# KegWasher_1_6_Schematic.net
KiCad netlist of a schematic drawn in EasyEDA
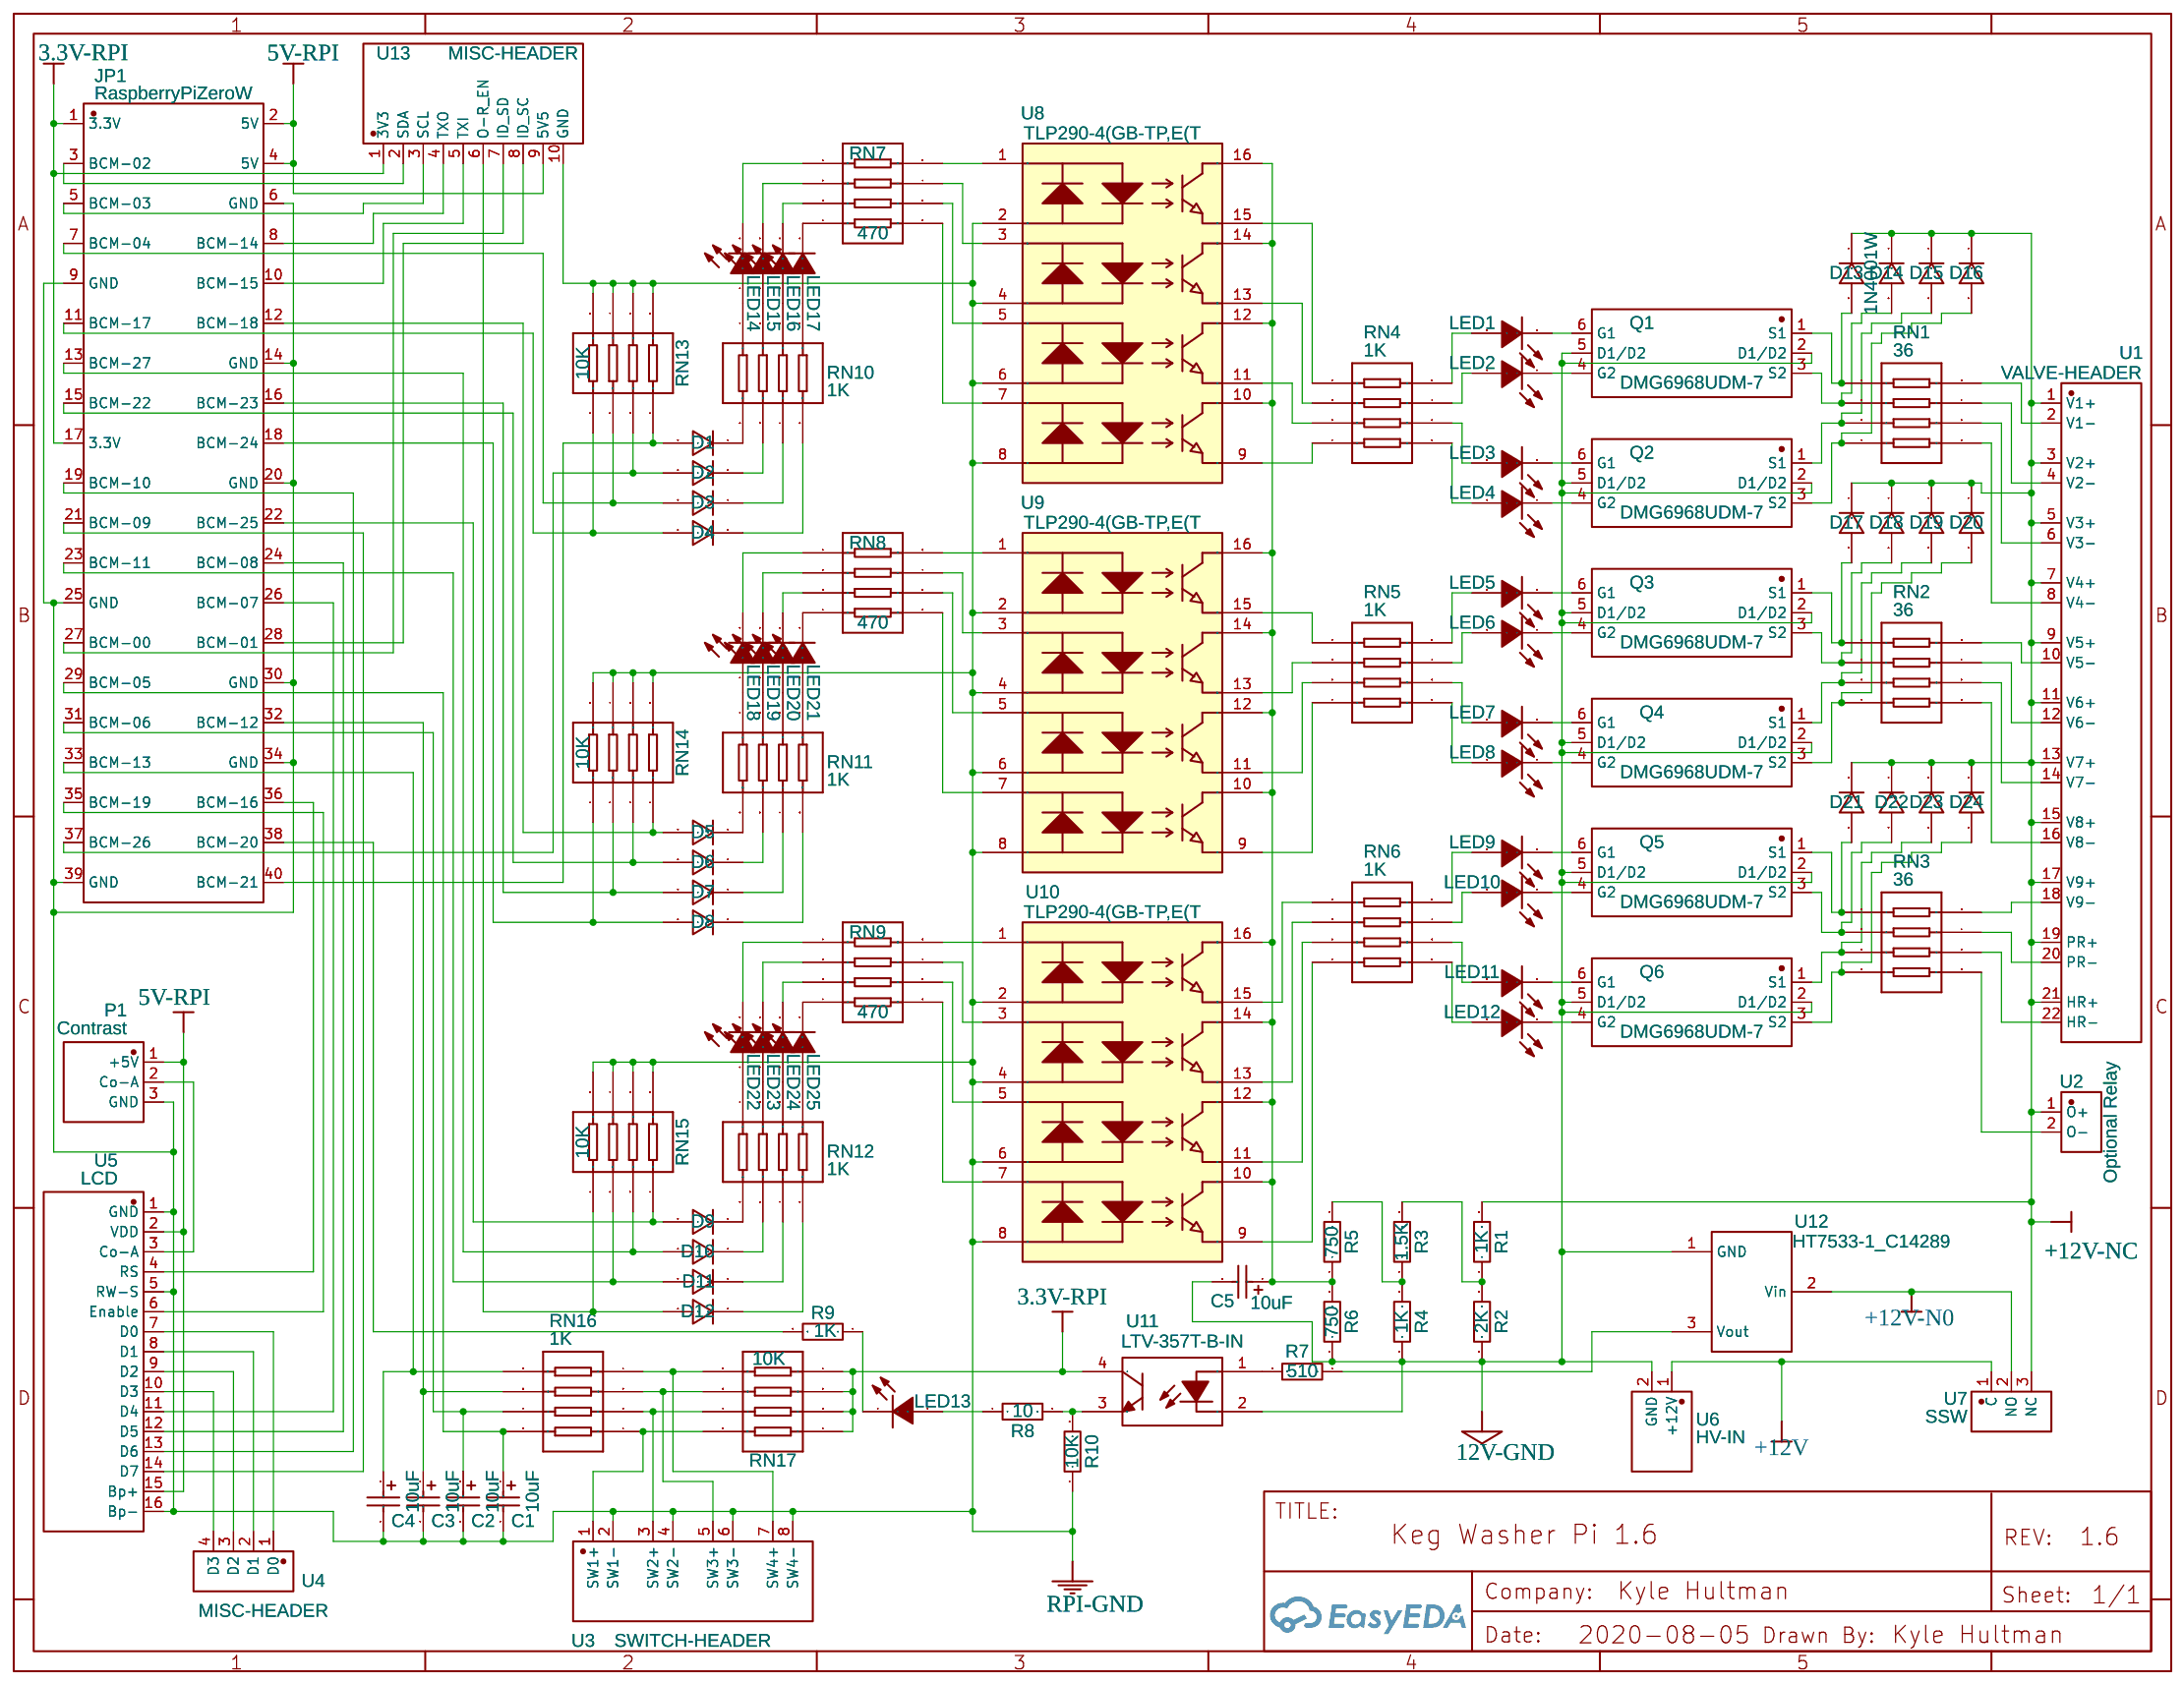
[diagram p0: schematic sheet]

(export (version "E")
  (design (tool "Eeschema 10.0.6"))
  (components
    (comp (ref "C1")
      (value "10uF")
      (fields
        (field (name "BOM_Manufacturer Part") "TAJA106K016RNJ")
        (field (name "BOM_Supplier Part") "C7171")
      )
      (libsource (lib "") (part "TAJA106K016RNJ"))
    )
    (comp (ref "C2")
      (value "10uF")
      (fields
        (field (name "BOM_Manufacturer Part") "TAJA106K016RNJ")
        (field (name "BOM_Supplier Part") "C7171")
      )
      (libsource (lib "") (part "TAJA106K016RNJ"))
    )
    (comp (ref "C3")
      (value "10uF")
      (fields
        (field (name "BOM_Manufacturer Part") "TAJA106K016RNJ")
        (field (name "BOM_Supplier Part") "C7171")
      )
      (libsource (lib "") (part "TAJA106K016RNJ"))
    )
    (comp (ref "C4")
      (value "10uF")
      (fields
        (field (name "BOM_Manufacturer Part") "TAJA106K016RNJ")
        (field (name "BOM_Supplier Part") "C7171")
      )
      (libsource (lib "") (part "TAJA106K016RNJ"))
    )
    (comp (ref "C5")
      (value "10uF")
      (fields
        (field (name "BOM_Manufacturer Part") "TAJA106K016RNJ")
        (field (name "BOM_Supplier Part") "C7171")
      )
      (libsource (lib "") (part "TAJA106K016RNJ_1"))
    )
    (comp (ref "D1")
      (value "1N4148W_C81598")
      (fields (field (name "BOM_Manufacturer Part") "1N4148W") (field (name "BOM_Supplier Part") "C81598"))
      (libsource (lib "") (part "1N4148W_C81598"))
    )
    (comp (ref "D2")
      (value "1N4148W_C81598")
      (fields (field (name "BOM_Manufacturer Part") "1N4148W") (field (name "BOM_Supplier Part") "C81598"))
      (libsource (lib "") (part "1N4148W_C81598"))
    )
    (comp (ref "D3")
      (value "1N4148W_C81598")
      (fields (field (name "BOM_Manufacturer Part") "1N4148W") (field (name "BOM_Supplier Part") "C81598"))
      (libsource (lib "") (part "1N4148W_C81598"))
    )
    (comp (ref "D4")
      (value "1N4148W_C81598")
      (fields (field (name "BOM_Manufacturer Part") "1N4148W") (field (name "BOM_Supplier Part") "C81598"))
      (libsource (lib "") (part "1N4148W_C81598"))
    )
    (comp (ref "D5")
      (value "1N4148W_C81598")
      (fields (field (name "BOM_Manufacturer Part") "1N4148W") (field (name "BOM_Supplier Part") "C81598"))
      (libsource (lib "") (part "1N4148W_C81598"))
    )
    (comp (ref "D6")
      (value "1N4148W_C81598")
      (fields (field (name "BOM_Manufacturer Part") "1N4148W") (field (name "BOM_Supplier Part") "C81598"))
      (libsource (lib "") (part "1N4148W_C81598"))
    )
    (comp (ref "D7")
      (value "1N4148W_C81598")
      (fields (field (name "BOM_Manufacturer Part") "1N4148W") (field (name "BOM_Supplier Part") "C81598"))
      (libsource (lib "") (part "1N4148W_C81598"))
    )
    (comp (ref "D8")
      (value "1N4148W_C81598")
      (fields (field (name "BOM_Manufacturer Part") "1N4148W") (field (name "BOM_Supplier Part") "C81598"))
      (libsource (lib "") (part "1N4148W_C81598"))
    )
    (comp (ref "D9")
      (value "1N4148W_C81598")
      (fields (field (name "BOM_Manufacturer Part") "1N4148W") (field (name "BOM_Supplier Part") "C81598"))
      (libsource (lib "") (part "1N4148W_C81598"))
    )
    (comp (ref "D10")
      (value "1N4148W_C81598")
      (fields (field (name "BOM_Manufacturer Part") "1N4148W") (field (name "BOM_Supplier Part") "C81598"))
      (libsource (lib "") (part "1N4148W_C81598"))
    )
    (comp (ref "D11")
      (value "1N4148W_C81598")
      (fields (field (name "BOM_Manufacturer Part") "1N4148W") (field (name "BOM_Supplier Part") "C81598"))
      (libsource (lib "") (part "1N4148W_C81598"))
    )
    (comp (ref "D12")
      (value "1N4148W_C81598")
      (fields (field (name "BOM_Manufacturer Part") "1N4148W") (field (name "BOM_Supplier Part") "C81598"))
      (libsource (lib "") (part "1N4148W_C81598"))
    )
    (comp (ref "D13")
      (value "1N4001W")
      (fields (field (name "BOM_Supplier Part") "C162732"))
      (libsource (lib "") (part "1N4001W"))
    )
    (comp (ref "D14")
      (value "1N4001W")
      (fields (field (name "BOM_Supplier Part") "C162732"))
      (libsource (lib "") (part "1N4001W"))
    )
    (comp (ref "D15")
      (value "1N4001W")
      (fields (field (name "BOM_Supplier Part") "C162732"))
      (libsource (lib "") (part "1N4001W"))
    )
    (comp (ref "D16")
      (value "1N4001W")
      (fields (field (name "BOM_Supplier Part") "C162732"))
      (libsource (lib "") (part "1N4001W"))
    )
    (comp (ref "D17")
      (value "1N4001W")
      (fields (field (name "BOM_Supplier Part") "C162732"))
      (libsource (lib "") (part "1N4001W"))
    )
    (comp (ref "D18")
      (value "1N4001W")
      (fields (field (name "BOM_Supplier Part") "C162732"))
      (libsource (lib "") (part "1N4001W"))
    )
    (comp (ref "D19")
      (value "1N4001W")
      (fields (field (name "BOM_Supplier Part") "C162732"))
      (libsource (lib "") (part "1N4001W"))
    )
    (comp (ref "D20")
      (value "1N4001W")
      (fields (field (name "BOM_Supplier Part") "C162732"))
      (libsource (lib "") (part "1N4001W"))
    )
    (comp (ref "D21")
      (value "1N4001W")
      (fields (field (name "BOM_Supplier Part") "C162732"))
      (libsource (lib "") (part "1N4001W"))
    )
    (comp (ref "D22")
      (value "1N4001W")
      (fields (field (name "BOM_Supplier Part") "C162732"))
      (libsource (lib "") (part "1N4001W"))
    )
    (comp (ref "D23")
      (value "1N4001W")
      (fields (field (name "BOM_Supplier Part") "C162732"))
      (libsource (lib "") (part "1N4001W"))
    )
    (comp (ref "D24")
      (value "1N4001W")
      (fields (field (name "BOM_Supplier Part") "C162732"))
      (libsource (lib "") (part "1N4001W"))
    )
    (comp (ref "JP1") (value "RaspberryPiZeroW") (libsource (lib "") (part "RaspberryPiZeroW")))
    (comp (ref "LED1")
      (value "17-21SUYC/TR8")
      (fields (field (name "BOM_Supplier Part") "C2296"))
      (libsource (lib "") (part "17-21SUYC/TR8"))
    )
    (comp (ref "LED2")
      (value "17-21SUYC/TR8")
      (fields (field (name "BOM_Supplier Part") "C2296"))
      (libsource (lib "") (part "17-21SUYC/TR8"))
    )
    (comp (ref "LED3")
      (value "17-21SUYC/TR8")
      (fields (field (name "BOM_Supplier Part") "C2296"))
      (libsource (lib "") (part "17-21SUYC/TR8"))
    )
    (comp (ref "LED4")
      (value "17-21SUYC/TR8")
      (fields (field (name "BOM_Supplier Part") "C2296"))
      (libsource (lib "") (part "17-21SUYC/TR8"))
    )
    (comp (ref "LED5")
      (value "17-21SUYC/TR8")
      (fields (field (name "BOM_Supplier Part") "C2296"))
      (libsource (lib "") (part "17-21SUYC/TR8"))
    )
    (comp (ref "LED6")
      (value "17-21SUYC/TR8")
      (fields (field (name "BOM_Supplier Part") "C2296"))
      (libsource (lib "") (part "17-21SUYC/TR8"))
    )
    (comp (ref "LED7")
      (value "17-21SUYC/TR8")
      (fields (field (name "BOM_Supplier Part") "C2296"))
      (libsource (lib "") (part "17-21SUYC/TR8"))
    )
    (comp (ref "LED8")
      (value "17-21SUYC/TR8")
      (fields (field (name "BOM_Supplier Part") "C2296"))
      (libsource (lib "") (part "17-21SUYC/TR8"))
    )
    (comp (ref "LED9")
      (value "17-21SUYC/TR8")
      (fields (field (name "BOM_Supplier Part") "C2296"))
      (libsource (lib "") (part "17-21SUYC/TR8"))
    )
    (comp (ref "LED10")
      (value "17-21SUYC/TR8")
      (fields (field (name "BOM_Supplier Part") "C2296"))
      (libsource (lib "") (part "17-21SUYC/TR8"))
    )
    (comp (ref "LED11")
      (value "17-21SUYC/TR8")
      (fields (field (name "BOM_Supplier Part") "C2296"))
      (libsource (lib "") (part "17-21SUYC/TR8"))
    )
    (comp (ref "LED12")
      (value "17-21SUYC/TR8")
      (fields (field (name "BOM_Supplier Part") "C2296"))
      (libsource (lib "") (part "17-21SUYC/TR8"))
    )
    (comp (ref "LED13")
      (value "17-21SUYC/TR8")
      (fields (field (name "BOM_Supplier Part") "C2296"))
      (libsource (lib "") (part "17-21SUYC/TR8_1"))
    )
    (comp (ref "LED14")
      (value "19-217/R6C-AL1M2VY/3T")
      (fields (field (name "BOM_Supplier Part") "C72044"))
      (libsource (lib "") (part "19-217/R6C-AL1M2VY/3T"))
    )
    (comp (ref "LED15")
      (value "19-217/R6C-AL1M2VY/3T")
      (fields (field (name "BOM_Supplier Part") "C72044"))
      (libsource (lib "") (part "19-217/R6C-AL1M2VY/3T"))
    )
    (comp (ref "LED16")
      (value "19-217/R6C-AL1M2VY/3T")
      (fields (field (name "BOM_Supplier Part") "C72044"))
      (libsource (lib "") (part "19-217/R6C-AL1M2VY/3T"))
    )
    (comp (ref "LED17")
      (value "19-217/R6C-AL1M2VY/3T")
      (fields (field (name "BOM_Supplier Part") "C72044"))
      (libsource (lib "") (part "19-217/R6C-AL1M2VY/3T"))
    )
    (comp (ref "LED18")
      (value "19-217/R6C-AL1M2VY/3T")
      (fields (field (name "BOM_Supplier Part") "C72044"))
      (libsource (lib "") (part "19-217/R6C-AL1M2VY/3T"))
    )
    (comp (ref "LED19")
      (value "19-217/R6C-AL1M2VY/3T")
      (fields (field (name "BOM_Supplier Part") "C72044"))
      (libsource (lib "") (part "19-217/R6C-AL1M2VY/3T"))
    )
    (comp (ref "LED20")
      (value "19-217/R6C-AL1M2VY/3T")
      (fields (field (name "BOM_Supplier Part") "C72044"))
      (libsource (lib "") (part "19-217/R6C-AL1M2VY/3T"))
    )
    (comp (ref "LED21")
      (value "19-217/R6C-AL1M2VY/3T")
      (fields (field (name "BOM_Supplier Part") "C72044"))
      (libsource (lib "") (part "19-217/R6C-AL1M2VY/3T"))
    )
    (comp (ref "LED22")
      (value "19-217/R6C-AL1M2VY/3T")
      (fields (field (name "BOM_Supplier Part") "C72044"))
      (libsource (lib "") (part "19-217/R6C-AL1M2VY/3T"))
    )
    (comp (ref "LED23")
      (value "19-217/R6C-AL1M2VY/3T")
      (fields (field (name "BOM_Supplier Part") "C72044"))
      (libsource (lib "") (part "19-217/R6C-AL1M2VY/3T"))
    )
    (comp (ref "LED24")
      (value "19-217/R6C-AL1M2VY/3T")
      (fields (field (name "BOM_Supplier Part") "C72044"))
      (libsource (lib "") (part "19-217/R6C-AL1M2VY/3T"))
    )
    (comp (ref "LED25")
      (value "19-217/R6C-AL1M2VY/3T")
      (fields (field (name "BOM_Supplier Part") "C72044"))
      (libsource (lib "") (part "19-217/R6C-AL1M2VY/3T"))
    )
    (comp (ref "P1") (value "Contrast") (libsource (lib "") (part "Contrast")))
    (comp (ref "Q1")
      (value "DMG6968UDM-7")
      (fields (field (name "BOM_Supplier Part") "C151635"))
      (libsource (lib "") (part "DMG6968UDM-7"))
    )
    (comp (ref "Q2")
      (value "DMG6968UDM-7")
      (fields (field (name "BOM_Supplier Part") "C151635"))
      (libsource (lib "") (part "DMG6968UDM-7"))
    )
    (comp (ref "Q3")
      (value "DMG6968UDM-7")
      (fields (field (name "BOM_Supplier Part") "C151635"))
      (libsource (lib "") (part "DMG6968UDM-7"))
    )
    (comp (ref "Q4")
      (value "DMG6968UDM-7")
      (fields (field (name "BOM_Supplier Part") "C151635"))
      (libsource (lib "") (part "DMG6968UDM-7"))
    )
    (comp (ref "Q5")
      (value "DMG6968UDM-7")
      (fields (field (name "BOM_Supplier Part") "C151635"))
      (libsource (lib "") (part "DMG6968UDM-7"))
    )
    (comp (ref "Q6")
      (value "DMG6968UDM-7")
      (fields (field (name "BOM_Supplier Part") "C151635"))
      (libsource (lib "") (part "DMG6968UDM-7"))
    )
    (comp (ref "R1")
      (value "1K")
      (fields
        (field (name "BOM_Manufacturer Part") "0805W8F1001T5E")
        (field (name "BOM_Supplier Part") "C17513")
      )
      (libsource (lib "") (part "0805W8F1001T5E_1"))
    )
    (comp (ref "R2")
      (value "2K")
      (fields
        (field (name "BOM_Manufacturer Part") "0805W8F2001T5E")
        (field (name "BOM_Supplier Part") "C17604")
      )
      (libsource (lib "") (part "0805W8F2001T5E"))
    )
    (comp (ref "R3")
      (value "1.5K")
      (fields
        (field (name "BOM_Manufacturer Part") "0805W8F1501T5E")
        (field (name "BOM_Supplier Part") "C4310")
      )
      (libsource (lib "") (part "0805W8F1501T5E"))
    )
    (comp (ref "R4")
      (value "1K")
      (fields
        (field (name "BOM_Manufacturer Part") "0805W8F1001T5E")
        (field (name "BOM_Supplier Part") "C17513")
      )
      (libsource (lib "") (part "0805W8F1001T5E_1"))
    )
    (comp (ref "R5")
      (value "750")
      (fields
        (field (name "BOM_Manufacturer Part") "0603WAF7500T5E")
        (field (name "BOM_Supplier Part") "C23241")
      )
      (libsource (lib "") (part "0603WAF7500T5E"))
    )
    (comp (ref "R6")
      (value "750")
      (fields
        (field (name "BOM_Manufacturer Part") "0603WAF7500T5E")
        (field (name "BOM_Supplier Part") "C23241")
      )
      (libsource (lib "") (part "0603WAF7500T5E"))
    )
    (comp (ref "R7")
      (value "510")
      (fields
        (field (name "BOM_Manufacturer Part") "0603WAF5100T5E")
        (field (name "BOM_Supplier Part") "C23193")
      )
      (libsource (lib "") (part "0603WAF5100T5E"))
    )
    (comp (ref "R8")
      (value "10")
      (fields
        (field (name "BOM_Manufacturer Part") "0603WAF100JT5E")
        (field (name "BOM_Supplier Part") "C22859")
      )
      (libsource (lib "") (part "0603WAF100JT5E"))
    )
    (comp (ref "R9")
      (value "1K")
      (fields
        (field (name "BOM_Manufacturer Part") "0805W8F1001T5E")
        (field (name "BOM_Supplier Part") "C17513")
      )
      (libsource (lib "") (part "0805W8F1001T5E"))
    )
    (comp (ref "R10")
      (value "10K")
      (fields
        (field (name "BOM_Manufacturer Part") "1206W4F1002T5E")
        (field (name "BOM_Supplier Part") "C17902")
      )
      (libsource (lib "") (part "1206W4F1002T5E"))
    )
    (comp (ref "RN1")
      (value "36")
      (fields
        (field (name "BOM_Manufacturer Part") "4D02WGJ0360TCE")
        (field (name "BOM_Supplier Part") "C25502")
      )
      (libsource (lib "") (part "4D02WGJ0360TCE"))
    )
    (comp (ref "RN2")
      (value "36")
      (fields
        (field (name "BOM_Manufacturer Part") "4D02WGJ0360TCE")
        (field (name "BOM_Supplier Part") "C25502")
      )
      (libsource (lib "") (part "4D02WGJ0360TCE"))
    )
    (comp (ref "RN3")
      (value "36")
      (fields
        (field (name "BOM_Manufacturer Part") "4D02WGJ0360TCE")
        (field (name "BOM_Supplier Part") "C25502")
      )
      (libsource (lib "") (part "4D02WGJ0360TCE"))
    )
    (comp (ref "RN4")
      (value "1K")
      (fields
        (field (name "BOM_Manufacturer Part") "4D02WGJ0102TCE")
        (field (name "BOM_Supplier Part") "C25726")
      )
      (libsource (lib "") (part "4D02WGJ0102TCE"))
    )
    (comp (ref "RN5")
      (value "1K")
      (fields
        (field (name "BOM_Manufacturer Part") "4D02WGJ0102TCE")
        (field (name "BOM_Supplier Part") "C25726")
      )
      (libsource (lib "") (part "4D02WGJ0102TCE"))
    )
    (comp (ref "RN6")
      (value "1K")
      (fields
        (field (name "BOM_Manufacturer Part") "4D02WGJ0102TCE")
        (field (name "BOM_Supplier Part") "C25726")
      )
      (libsource (lib "") (part "4D02WGJ0102TCE"))
    )
    (comp (ref "RN7")
      (value "470")
      (fields
        (field (name "BOM_Manufacturer Part") "4D03WGJ0471T5E")
        (field (name "BOM_Supplier Part") "C25510")
      )
      (libsource (lib "") (part "4D03WGJ0471T5E"))
    )
    (comp (ref "RN8")
      (value "470")
      (fields
        (field (name "BOM_Manufacturer Part") "4D03WGJ0471T5E")
        (field (name "BOM_Supplier Part") "C25510")
      )
      (libsource (lib "") (part "4D03WGJ0471T5E"))
    )
    (comp (ref "RN9")
      (value "470")
      (fields
        (field (name "BOM_Manufacturer Part") "4D03WGJ0471T5E")
        (field (name "BOM_Supplier Part") "C25510")
      )
      (libsource (lib "") (part "4D03WGJ0471T5E"))
    )
    (comp (ref "RN10")
      (value "1K")
      (fields
        (field (name "BOM_Manufacturer Part") "4D02WGJ0102TCE")
        (field (name "BOM_Supplier Part") "C25726")
      )
      (libsource (lib "") (part "4D02WGJ0102TCE_2"))
    )
    (comp (ref "RN11")
      (value "1K")
      (fields
        (field (name "BOM_Manufacturer Part") "4D02WGJ0102TCE")
        (field (name "BOM_Supplier Part") "C25726")
      )
      (libsource (lib "") (part "4D02WGJ0102TCE_2"))
    )
    (comp (ref "RN12")
      (value "1K")
      (fields
        (field (name "BOM_Manufacturer Part") "4D02WGJ0102TCE")
        (field (name "BOM_Supplier Part") "C25726")
      )
      (libsource (lib "") (part "4D02WGJ0102TCE_2"))
    )
    (comp (ref "RN13")
      (value "10K")
      (fields
        (field (name "BOM_Manufacturer Part") "4D02WGJ0103TCE")
        (field (name "BOM_Supplier Part") "C25725")
      )
      (libsource (lib "") (part "4D02WGJ0103TCE"))
    )
    (comp (ref "RN14")
      (value "10K")
      (fields
        (field (name "BOM_Manufacturer Part") "4D02WGJ0103TCE")
        (field (name "BOM_Supplier Part") "C25725")
      )
      (libsource (lib "") (part "4D02WGJ0103TCE"))
    )
    (comp (ref "RN15")
      (value "10K")
      (fields
        (field (name "BOM_Manufacturer Part") "4D02WGJ0103TCE")
        (field (name "BOM_Supplier Part") "C25725")
      )
      (libsource (lib "") (part "4D02WGJ0103TCE"))
    )
    (comp (ref "RN16")
      (value "1K")
      (fields
        (field (name "BOM_Manufacturer Part") "4D02WGJ0102TCE")
        (field (name "BOM_Supplier Part") "C25726")
      )
      (libsource (lib "") (part "4D02WGJ0102TCE_1"))
    )
    (comp (ref "RN17")
      (value "10K")
      (fields
        (field (name "BOM_Manufacturer Part") "4D02WGJ0103TCE")
        (field (name "BOM_Supplier Part") "C25725")
      )
      (libsource (lib "") (part "4D02WGJ0103TCE_1"))
    )
    (comp (ref "U1") (value "VALVE-HEADER") (libsource (lib "") (part "VALVE-HEADER")))
    (comp (ref "U2") (value "Optional Relay") (libsource (lib "") (part "Optional Relay")))
    (comp (ref "U3") (value "SWITCH-HEADER") (libsource (lib "") (part "SWITCH-HEADER")))
    (comp (ref "U4") (value "MISC-HEADER") (libsource (lib "") (part "MISC-HEADER")))
    (comp (ref "U5") (value "LCD") (libsource (lib "") (part "LCD")))
    (comp (ref "U6") (value "HV-IN") (libsource (lib "") (part "HV-IN")))
    (comp (ref "U7") (value "SSW") (libsource (lib "") (part "SSW")))
    (comp (ref "U8")
      (value "TLP290-4(GB-TP,E(T")
      (fields (field (name "BOM_Supplier Part") "C39031"))
      (libsource (lib "") (part "TLP290-4(GB-TP,E(T"))
    )
    (comp (ref "U9")
      (value "TLP290-4(GB-TP,E(T")
      (fields (field (name "BOM_Supplier Part") "C39031"))
      (libsource (lib "") (part "TLP290-4(GB-TP,E(T"))
    )
    (comp (ref "U10")
      (value "TLP290-4(GB-TP,E(T")
      (fields (field (name "BOM_Supplier Part") "C39031"))
      (libsource (lib "") (part "TLP290-4(GB-TP,E(T"))
    )
    (comp (ref "U11")
      (value "LTV-357T-B-IN")
      (fields (field (name "BOM_Supplier Part") "C406713"))
      (libsource (lib "") (part "LTV-357T-B-IN"))
    )
    (comp (ref "U12")
      (value "HT7533-1_C14289")
      (fields (field (name "BOM_Manufacturer Part") "HT7533-1") (field (name "BOM_Supplier Part") "C14289"))
      (libsource (lib "") (part "HT7533-1_C14289"))
    )
    (comp (ref "U13") (value "MISC-HEADER") (libsource (lib "") (part "MISC-HEADER_1")))
  )
  (nets
    (net (code "1") (name "+12V") (class "Default")
      (node (ref "U6") (pin "1") (pinfunction "+12V_1") (pintype "unspecified"))
      (node (ref "U7") (pin "1") (pinfunction "C_1") (pintype "unspecified"))
    )
    (net (code "2") (name "+12V-N0") (class "Default")
      (node (ref "U12") (pin "2") (pinfunction "Vin_2") (pintype "unspecified"))
      (node (ref "U7") (pin "2") (pinfunction "NO_2") (pintype "unspecified"))
    )
    (net (code "3") (name "+12V-NC") (class "Default")
      (node (ref "D13") (pin "1") (pinfunction "C_1") (pintype "unspecified"))
      (node (ref "D14") (pin "1") (pinfunction "C_1") (pintype "unspecified"))
      (node (ref "D15") (pin "1") (pinfunction "C_1") (pintype "unspecified"))
      (node (ref "D16") (pin "1") (pinfunction "C_1") (pintype "unspecified"))
      (node (ref "D17") (pin "1") (pinfunction "C_1") (pintype "unspecified"))
      (node (ref "D18") (pin "1") (pinfunction "C_1") (pintype "unspecified"))
      (node (ref "D19") (pin "1") (pinfunction "C_1") (pintype "unspecified"))
      (node (ref "D20") (pin "1") (pinfunction "C_1") (pintype "unspecified"))
      (node (ref "D21") (pin "1") (pinfunction "C_1") (pintype "unspecified"))
      (node (ref "D22") (pin "1") (pinfunction "C_1") (pintype "unspecified"))
      (node (ref "D23") (pin "1") (pinfunction "C_1") (pintype "unspecified"))
      (node (ref "D24") (pin "1") (pinfunction "C_1") (pintype "unspecified"))
      (node (ref "R1") (pin "2") (pinfunction "2_2") (pintype "input"))
      (node (ref "U1") (pin "1") (pinfunction "V1+_1") (pintype "unspecified"))
      (node (ref "U1") (pin "11") (pinfunction "V6+_11") (pintype "unspecified"))
      (node (ref "U1") (pin "13") (pinfunction "V7+_13") (pintype "unspecified"))
      (node (ref "U1") (pin "15") (pinfunction "V8+_15") (pintype "unspecified"))
      (node (ref "U1") (pin "17") (pinfunction "V9+_17") (pintype "unspecified"))
      (node (ref "U1") (pin "19") (pinfunction "PR+_19") (pintype "unspecified"))
      (node (ref "U1") (pin "21") (pinfunction "HR+_21") (pintype "unspecified"))
      (node (ref "U1") (pin "3") (pinfunction "V2+_3") (pintype "unspecified"))
      (node (ref "U1") (pin "5") (pinfunction "V3+_5") (pintype "unspecified"))
      (node (ref "U1") (pin "7") (pinfunction "V4+_7") (pintype "unspecified"))
      (node (ref "U1") (pin "9") (pinfunction "V5+_9") (pintype "unspecified"))
      (node (ref "U2") (pin "1") (pinfunction "O+_1") (pintype "unspecified"))
      (node (ref "U7") (pin "3") (pinfunction "NC_3") (pintype "unspecified"))
    )
    (net (code "4") (name "3.3V-RPI") (class "Default")
      (node (ref "JP1") (pin "1") (pinfunction "3.3V_1") (pintype "unspecified"))
      (node (ref "JP1") (pin "17") (pinfunction "3.3V_17") (pintype "unspecified"))
      (node (ref "RN17") (pin "1") (pinfunction "1_1") (pintype "input"))
      (node (ref "RN17") (pin "2") (pinfunction "2_2") (pintype "input"))
      (node (ref "RN17") (pin "3") (pinfunction "3_3") (pintype "input"))
      (node (ref "RN17") (pin "4") (pinfunction "4_4") (pintype "input"))
      (node (ref "U11") (pin "4") (pinfunction "4_4") (pintype "unspecified"))
      (node (ref "U13") (pin "1") (pinfunction "3V3_1") (pintype "unspecified"))
    )
    (net (code "5") (name "5V-RPI") (class "Default")
      (node (ref "JP1") (pin "2") (pinfunction "5V_2") (pintype "unspecified"))
      (node (ref "JP1") (pin "4") (pinfunction "5V_4") (pintype "unspecified"))
      (node (ref "P1") (pin "1") (pinfunction "+5V_1") (pintype "unspecified"))
      (node (ref "U13") (pin "9") (pinfunction "5V5_9") (pintype "unspecified"))
      (node (ref "U5") (pin "15") (pinfunction "Bp+_15") (pintype "unspecified"))
      (node (ref "U5") (pin "2") (pinfunction "VDD_2") (pintype "unspecified"))
    )
    (net (code "6") (name "12V-GND") (class "Default")
      (node (ref "C5") (pin "2") (pinfunction "2_2") (pintype "input"))
      (node (ref "Q1") (pin "2") (pinfunction "D1/D2_2") (pintype "unspecified"))
      (node (ref "Q1") (pin "5") (pinfunction "D1/D2_5") (pintype "unspecified"))
      (node (ref "Q2") (pin "2") (pinfunction "D1/D2_2") (pintype "unspecified"))
      (node (ref "Q2") (pin "5") (pinfunction "D1/D2_5") (pintype "unspecified"))
      (node (ref "Q3") (pin "2") (pinfunction "D1/D2_2") (pintype "unspecified"))
      (node (ref "Q3") (pin "5") (pinfunction "D1/D2_5") (pintype "unspecified"))
      (node (ref "Q4") (pin "2") (pinfunction "D1/D2_2") (pintype "unspecified"))
      (node (ref "Q4") (pin "5") (pinfunction "D1/D2_5") (pintype "unspecified"))
      (node (ref "Q5") (pin "2") (pinfunction "D1/D2_2") (pintype "unspecified"))
      (node (ref "Q5") (pin "5") (pinfunction "D1/D2_5") (pintype "unspecified"))
      (node (ref "Q6") (pin "2") (pinfunction "D1/D2_2") (pintype "unspecified"))
      (node (ref "Q6") (pin "5") (pinfunction "D1/D2_5") (pintype "unspecified"))
      (node (ref "R2") (pin "1") (pinfunction "1_1") (pintype "input"))
      (node (ref "R4") (pin "1") (pinfunction "1_1") (pintype "input"))
      (node (ref "R6") (pin "1") (pinfunction "1_1") (pintype "input"))
      (node (ref "U11") (pin "2") (pinfunction "2_2") (pintype "unspecified"))
      (node (ref "U12") (pin "1") (pinfunction "GND_1") (pintype "unspecified"))
      (node (ref "U6") (pin "2") (pinfunction "GND_2") (pintype "unspecified"))
    )
    (net (code "7") (name "Net-(C5-Pad1)") (class "Default")
      (node (ref "C5") (pin "1") (pinfunction "1_1") (pintype "input"))
      (node (ref "R5") (pin "1") (pinfunction "1_1") (pintype "input"))
      (node (ref "R6") (pin "2") (pinfunction "2_2") (pintype "input"))
      (node (ref "U10") (pin "10") (pinfunction "10_10") (pintype "input"))
      (node (ref "U10") (pin "12") (pinfunction "12_12") (pintype "input"))
      (node (ref "U10") (pin "14") (pinfunction "14_14") (pintype "input"))
      (node (ref "U10") (pin "16") (pinfunction "16_16") (pintype "input"))
      (node (ref "U8") (pin "10") (pinfunction "10_10") (pintype "input"))
      (node (ref "U8") (pin "12") (pinfunction "12_12") (pintype "input"))
      (node (ref "U8") (pin "14") (pinfunction "14_14") (pintype "input"))
      (node (ref "U8") (pin "16") (pinfunction "16_16") (pintype "input"))
      (node (ref "U9") (pin "10") (pinfunction "10_10") (pintype "input"))
      (node (ref "U9") (pin "12") (pinfunction "12_12") (pintype "input"))
      (node (ref "U9") (pin "14") (pinfunction "14_14") (pintype "input"))
      (node (ref "U9") (pin "16") (pinfunction "16_16") (pintype "input"))
    )
    (net (code "8") (name "Net-(D1-A)") (class "Default")
      (node (ref "D1") (pin "2") (pinfunction "A_2") (pintype "unspecified"))
      (node (ref "JP1") (pin "40") (pinfunction "BCM-21_40") (pintype "unspecified"))
      (node (ref "RN13") (pin "4") (pinfunction "4_4") (pintype "input"))
    )
    (net (code "9") (name "Net-(D1-K)") (class "Default")
      (node (ref "D1") (pin "1") (pinfunction "K_1") (pintype "unspecified"))
      (node (ref "RN10") (pin "5") (pinfunction "5_5") (pintype "input"))
    )
    (net (code "10") (name "Net-(D2-A)") (class "Default")
      (node (ref "D2") (pin "2") (pinfunction "A_2") (pintype "unspecified"))
      (node (ref "JP1") (pin "37") (pinfunction "BCM-26_37") (pintype "unspecified"))
      (node (ref "RN13") (pin "3") (pinfunction "3_3") (pintype "input"))
    )
    (net (code "11") (name "Net-(D2-K)") (class "Default")
      (node (ref "D2") (pin "1") (pinfunction "K_1") (pintype "unspecified"))
      (node (ref "RN10") (pin "6") (pinfunction "6_6") (pintype "input"))
    )
    (net (code "12") (name "Net-(D3-A)") (class "Default")
      (node (ref "D3") (pin "2") (pinfunction "A_2") (pintype "unspecified"))
      (node (ref "JP1") (pin "7") (pinfunction "BCM-04_7") (pintype "unspecified"))
      (node (ref "RN13") (pin "2") (pinfunction "2_2") (pintype "input"))
    )
    (net (code "13") (name "Net-(D3-K)") (class "Default")
      (node (ref "D3") (pin "1") (pinfunction "K_1") (pintype "unspecified"))
      (node (ref "RN10") (pin "7") (pinfunction "7_7") (pintype "input"))
    )
    (net (code "14") (name "Net-(D4-A)") (class "Default")
      (node (ref "D4") (pin "2") (pinfunction "A_2") (pintype "unspecified"))
      (node (ref "JP1") (pin "11") (pinfunction "BCM-17_11") (pintype "unspecified"))
      (node (ref "RN13") (pin "1") (pinfunction "1_1") (pintype "input"))
    )
    (net (code "15") (name "Net-(D4-K)") (class "Default")
      (node (ref "D4") (pin "1") (pinfunction "K_1") (pintype "unspecified"))
      (node (ref "RN10") (pin "8") (pinfunction "8_8") (pintype "input"))
    )
    (net (code "16") (name "Net-(D5-A)") (class "Default")
      (node (ref "D5") (pin "2") (pinfunction "A_2") (pintype "unspecified"))
      (node (ref "JP1") (pin "12") (pinfunction "BCM-18_12") (pintype "unspecified"))
      (node (ref "RN14") (pin "4") (pinfunction "4_4") (pintype "input"))
    )
    (net (code "17") (name "Net-(D5-K)") (class "Default")
      (node (ref "D5") (pin "1") (pinfunction "K_1") (pintype "unspecified"))
      (node (ref "RN11") (pin "5") (pinfunction "5_5") (pintype "input"))
    )
    (net (code "18") (name "Net-(D6-A)") (class "Default")
      (node (ref "D6") (pin "2") (pinfunction "A_2") (pintype "unspecified"))
      (node (ref "JP1") (pin "15") (pinfunction "BCM-22_15") (pintype "unspecified"))
      (node (ref "RN14") (pin "3") (pinfunction "3_3") (pintype "input"))
    )
    (net (code "19") (name "Net-(D6-K)") (class "Default")
      (node (ref "D6") (pin "1") (pinfunction "K_1") (pintype "unspecified"))
      (node (ref "RN11") (pin "6") (pinfunction "6_6") (pintype "input"))
    )
    (net (code "20") (name "Net-(D7-A)") (class "Default")
      (node (ref "D7") (pin "2") (pinfunction "A_2") (pintype "unspecified"))
      (node (ref "JP1") (pin "16") (pinfunction "BCM-23_16") (pintype "unspecified"))
      (node (ref "RN14") (pin "2") (pinfunction "2_2") (pintype "input"))
    )
    (net (code "21") (name "Net-(D7-K)") (class "Default")
      (node (ref "D7") (pin "1") (pinfunction "K_1") (pintype "unspecified"))
      (node (ref "RN11") (pin "7") (pinfunction "7_7") (pintype "input"))
    )
    (net (code "22") (name "Net-(D8-A)") (class "Default")
      (node (ref "D8") (pin "2") (pinfunction "A_2") (pintype "unspecified"))
      (node (ref "JP1") (pin "18") (pinfunction "BCM-24_18") (pintype "unspecified"))
      (node (ref "RN14") (pin "1") (pinfunction "1_1") (pintype "input"))
    )
    (net (code "23") (name "Net-(D8-K)") (class "Default")
      (node (ref "D8") (pin "1") (pinfunction "K_1") (pintype "unspecified"))
      (node (ref "RN11") (pin "8") (pinfunction "8_8") (pintype "input"))
    )
    (net (code "24") (name "Net-(D9-A)") (class "Default")
      (node (ref "D9") (pin "2") (pinfunction "A_2") (pintype "unspecified"))
      (node (ref "JP1") (pin "22") (pinfunction "BCM-25_22") (pintype "unspecified"))
      (node (ref "RN15") (pin "4") (pinfunction "4_4") (pintype "input"))
    )
    (net (code "25") (name "Net-(D9-K)") (class "Default")
      (node (ref "D9") (pin "1") (pinfunction "K_1") (pintype "unspecified"))
      (node (ref "RN12") (pin "5") (pinfunction "5_5") (pintype "input"))
    )
    (net (code "26") (name "Net-(D10-A)") (class "Default")
      (node (ref "D10") (pin "2") (pinfunction "A_2") (pintype "unspecified"))
      (node (ref "JP1") (pin "13") (pinfunction "BCM-27_13") (pintype "unspecified"))
      (node (ref "RN15") (pin "3") (pinfunction "3_3") (pintype "input"))
    )
    (net (code "27") (name "Net-(D10-K)") (class "Default")
      (node (ref "D10") (pin "1") (pinfunction "K_1") (pintype "unspecified"))
      (node (ref "RN12") (pin "6") (pinfunction "6_6") (pintype "input"))
    )
    (net (code "28") (name "Net-(D11-A)") (class "Default")
      (node (ref "D11") (pin "2") (pinfunction "A_2") (pintype "unspecified"))
      (node (ref "JP1") (pin "23") (pinfunction "BCM-11_23") (pintype "unspecified"))
      (node (ref "RN15") (pin "2") (pinfunction "2_2") (pintype "input"))
    )
    (net (code "29") (name "Net-(D11-K)") (class "Default")
      (node (ref "D11") (pin "1") (pinfunction "K_1") (pintype "unspecified"))
      (node (ref "RN12") (pin "7") (pinfunction "7_7") (pintype "input"))
    )
    (net (code "30") (name "Net-(D12-A)") (class "Default")
      (node (ref "D12") (pin "2") (pinfunction "A_2") (pintype "unspecified"))
      (node (ref "RN15") (pin "1") (pinfunction "1_1") (pintype "input"))
      (node (ref "U13") (pin "6") (pinfunction "O-R_EN_6") (pintype "unspecified"))
    )
    (net (code "31") (name "Net-(D12-K)") (class "Default")
      (node (ref "D12") (pin "1") (pinfunction "K_1") (pintype "unspecified"))
      (node (ref "RN12") (pin "8") (pinfunction "8_8") (pintype "input"))
    )
    (net (code "32") (name "Net-(D13-A)") (class "Default")
      (node (ref "D13") (pin "2") (pinfunction "A_2") (pintype "unspecified"))
      (node (ref "Q1") (pin "1") (pinfunction "S1_1") (pintype "unspecified"))
      (node (ref "RN1") (pin "1") (pinfunction "1_1") (pintype "input"))
    )
    (net (code "33") (name "Net-(D14-A)") (class "Default")
      (node (ref "D14") (pin "2") (pinfunction "A_2") (pintype "unspecified"))
      (node (ref "Q1") (pin "3") (pinfunction "S2_3") (pintype "unspecified"))
      (node (ref "RN1") (pin "2") (pinfunction "2_2") (pintype "input"))
    )
    (net (code "34") (name "Net-(D15-A)") (class "Default")
      (node (ref "D15") (pin "2") (pinfunction "A_2") (pintype "unspecified"))
      (node (ref "Q2") (pin "1") (pinfunction "S1_1") (pintype "unspecified"))
      (node (ref "RN1") (pin "3") (pinfunction "3_3") (pintype "input"))
    )
    (net (code "35") (name "Net-(D16-A)") (class "Default")
      (node (ref "D16") (pin "2") (pinfunction "A_2") (pintype "unspecified"))
      (node (ref "Q2") (pin "3") (pinfunction "S2_3") (pintype "unspecified"))
      (node (ref "RN1") (pin "4") (pinfunction "4_4") (pintype "input"))
    )
    (net (code "36") (name "Net-(D17-A)") (class "Default")
      (node (ref "D17") (pin "2") (pinfunction "A_2") (pintype "unspecified"))
      (node (ref "Q3") (pin "1") (pinfunction "S1_1") (pintype "unspecified"))
      (node (ref "RN2") (pin "1") (pinfunction "1_1") (pintype "input"))
    )
    (net (code "37") (name "Net-(D18-A)") (class "Default")
      (node (ref "D18") (pin "2") (pinfunction "A_2") (pintype "unspecified"))
      (node (ref "Q3") (pin "3") (pinfunction "S2_3") (pintype "unspecified"))
      (node (ref "RN2") (pin "2") (pinfunction "2_2") (pintype "input"))
    )
    (net (code "38") (name "Net-(D19-A)") (class "Default")
      (node (ref "D19") (pin "2") (pinfunction "A_2") (pintype "unspecified"))
      (node (ref "Q4") (pin "1") (pinfunction "S1_1") (pintype "unspecified"))
      (node (ref "RN2") (pin "3") (pinfunction "3_3") (pintype "input"))
    )
    (net (code "39") (name "Net-(D20-A)") (class "Default")
      (node (ref "D20") (pin "2") (pinfunction "A_2") (pintype "unspecified"))
      (node (ref "Q4") (pin "3") (pinfunction "S2_3") (pintype "unspecified"))
      (node (ref "RN2") (pin "4") (pinfunction "4_4") (pintype "input"))
    )
    (net (code "40") (name "Net-(D21-A)") (class "Default")
      (node (ref "D21") (pin "2") (pinfunction "A_2") (pintype "unspecified"))
      (node (ref "Q5") (pin "1") (pinfunction "S1_1") (pintype "unspecified"))
      (node (ref "RN3") (pin "1") (pinfunction "1_1") (pintype "input"))
    )
    (net (code "41") (name "Net-(D22-A)") (class "Default")
      (node (ref "D22") (pin "2") (pinfunction "A_2") (pintype "unspecified"))
      (node (ref "Q5") (pin "3") (pinfunction "S2_3") (pintype "unspecified"))
      (node (ref "RN3") (pin "2") (pinfunction "2_2") (pintype "input"))
    )
    (net (code "42") (name "Net-(D23-A)") (class "Default")
      (node (ref "D23") (pin "2") (pinfunction "A_2") (pintype "unspecified"))
      (node (ref "Q6") (pin "1") (pinfunction "S1_1") (pintype "unspecified"))
      (node (ref "RN3") (pin "3") (pinfunction "3_3") (pintype "input"))
    )
    (net (code "43") (name "Net-(D24-A)") (class "Default")
      (node (ref "D24") (pin "2") (pinfunction "A_2") (pintype "unspecified"))
      (node (ref "Q6") (pin "3") (pinfunction "S2_3") (pintype "unspecified"))
      (node (ref "RN3") (pin "4") (pinfunction "4_4") (pintype "input"))
    )
    (net (code "44") (name "Net-(JP1-BCM-00)") (class "Default")
      (node (ref "JP1") (pin "27") (pinfunction "BCM-00_27") (pintype "unspecified"))
      (node (ref "U13") (pin "7") (pinfunction "ID_SD_7") (pintype "unspecified"))
    )
    (net (code "45") (name "Net-(JP1-BCM-01)") (class "Default")
      (node (ref "JP1") (pin "28") (pinfunction "BCM-01_28") (pintype "unspecified"))
      (node (ref "U13") (pin "8") (pinfunction "ID_SC_8") (pintype "unspecified"))
    )
    (net (code "46") (name "Net-(JP1-BCM-02)") (class "Default")
      (node (ref "JP1") (pin "3") (pinfunction "BCM-02_3") (pintype "unspecified"))
      (node (ref "U13") (pin "2") (pinfunction "SDA_2") (pintype "unspecified"))
    )
    (net (code "47") (name "Net-(JP1-BCM-03)") (class "Default")
      (node (ref "JP1") (pin "5") (pinfunction "BCM-03_5") (pintype "unspecified"))
      (node (ref "U13") (pin "3") (pinfunction "SCL_3") (pintype "unspecified"))
    )
    (net (code "48") (name "Net-(JP1-BCM-05)") (class "Default")
      (node (ref "C1") (pin "1") (pinfunction "1_1") (pintype "input"))
      (node (ref "JP1") (pin "29") (pinfunction "BCM-05_29") (pintype "unspecified"))
      (node (ref "RN16") (pin "8") (pinfunction "8_8") (pintype "input"))
    )
    (net (code "49") (name "Net-(JP1-BCM-06)") (class "Default")
      (node (ref "C2") (pin "1") (pinfunction "1_1") (pintype "input"))
      (node (ref "JP1") (pin "31") (pinfunction "BCM-06_31") (pintype "unspecified"))
      (node (ref "RN16") (pin "7") (pinfunction "7_7") (pintype "input"))
    )
    (net (code "50") (name "Net-(JP1-BCM-07)") (class "Default")
      (node (ref "JP1") (pin "26") (pinfunction "BCM-07_26") (pintype "unspecified"))
      (node (ref "U5") (pin "11") (pinfunction "D4_11") (pintype "unspecified"))
    )
    (net (code "51") (name "Net-(JP1-BCM-08)") (class "Default")
      (node (ref "JP1") (pin "24") (pinfunction "BCM-08_24") (pintype "unspecified"))
      (node (ref "U5") (pin "12") (pinfunction "D5_12") (pintype "unspecified"))
    )
    (net (code "52") (name "Net-(JP1-BCM-09)") (class "Default")
      (node (ref "JP1") (pin "21") (pinfunction "BCM-09_21") (pintype "unspecified"))
      (node (ref "U5") (pin "14") (pinfunction "D7_14") (pintype "unspecified"))
    )
    (net (code "53") (name "Net-(JP1-BCM-10)") (class "Default")
      (node (ref "JP1") (pin "19") (pinfunction "BCM-10_19") (pintype "unspecified"))
      (node (ref "U5") (pin "13") (pinfunction "D6_13") (pintype "unspecified"))
    )
    (net (code "54") (name "Net-(JP1-BCM-12)") (class "Default")
      (node (ref "C3") (pin "1") (pinfunction "1_1") (pintype "input"))
      (node (ref "JP1") (pin "32") (pinfunction "BCM-12_32") (pintype "unspecified"))
      (node (ref "RN16") (pin "6") (pinfunction "6_6") (pintype "input"))
    )
    (net (code "55") (name "Net-(JP1-BCM-13)") (class "Default")
      (node (ref "C4") (pin "1") (pinfunction "1_1") (pintype "input"))
      (node (ref "JP1") (pin "33") (pinfunction "BCM-13_33") (pintype "unspecified"))
      (node (ref "RN16") (pin "5") (pinfunction "5_5") (pintype "input"))
    )
    (net (code "56") (name "Net-(JP1-BCM-14)") (class "Default")
      (node (ref "JP1") (pin "8") (pinfunction "BCM-14_8") (pintype "unspecified"))
      (node (ref "U13") (pin "4") (pinfunction "TXO_4") (pintype "unspecified"))
    )
    (net (code "57") (name "Net-(JP1-BCM-15)") (class "Default")
      (node (ref "JP1") (pin "10") (pinfunction "BCM-15_10") (pintype "unspecified"))
      (node (ref "U13") (pin "5") (pinfunction "TXI_5") (pintype "unspecified"))
    )
    (net (code "58") (name "Net-(JP1-BCM-16)") (class "Default")
      (node (ref "JP1") (pin "36") (pinfunction "BCM-16_36") (pintype "unspecified"))
      (node (ref "U5") (pin "4") (pinfunction "RS_4") (pintype "unspecified"))
    )
    (net (code "59") (name "Net-(JP1-BCM-19)") (class "Default")
      (node (ref "JP1") (pin "35") (pinfunction "BCM-19_35") (pintype "unspecified"))
      (node (ref "U5") (pin "6") (pinfunction "Enable_6") (pintype "unspecified"))
    )
    (net (code "60") (name "Net-(JP1-BCM-20)") (class "Default")
      (node (ref "JP1") (pin "38") (pinfunction "BCM-20_38") (pintype "unspecified"))
      (node (ref "R9") (pin "2") (pinfunction "2_2") (pintype "input"))
    )
    (net (code "61") (name "Net-(LED1-+)") (class "Default")
      (node (ref "LED1") (pin "2") (pinfunction "+_2") (pintype "unspecified"))
      (node (ref "RN4") (pin "8") (pinfunction "8_8") (pintype "input"))
    )
    (net (code "62") (name "Net-(LED1--)") (class "Default")
      (node (ref "LED1") (pin "1") (pinfunction "-_1") (pintype "unspecified"))
      (node (ref "Q1") (pin "6") (pinfunction "G1_6") (pintype "unspecified"))
    )
    (net (code "63") (name "Net-(LED2-+)") (class "Default")
      (node (ref "LED2") (pin "2") (pinfunction "+_2") (pintype "unspecified"))
      (node (ref "RN4") (pin "7") (pinfunction "7_7") (pintype "input"))
    )
    (net (code "64") (name "Net-(LED2--)") (class "Default")
      (node (ref "LED2") (pin "1") (pinfunction "-_1") (pintype "unspecified"))
      (node (ref "Q1") (pin "4") (pinfunction "G2_4") (pintype "unspecified"))
    )
    (net (code "65") (name "Net-(LED3-+)") (class "Default")
      (node (ref "LED3") (pin "2") (pinfunction "+_2") (pintype "unspecified"))
      (node (ref "RN4") (pin "6") (pinfunction "6_6") (pintype "input"))
    )
    (net (code "66") (name "Net-(LED3--)") (class "Default")
      (node (ref "LED3") (pin "1") (pinfunction "-_1") (pintype "unspecified"))
      (node (ref "Q2") (pin "6") (pinfunction "G1_6") (pintype "unspecified"))
    )
    (net (code "67") (name "Net-(LED4-+)") (class "Default")
      (node (ref "LED4") (pin "2") (pinfunction "+_2") (pintype "unspecified"))
      (node (ref "RN4") (pin "5") (pinfunction "5_5") (pintype "input"))
    )
    (net (code "68") (name "Net-(LED4--)") (class "Default")
      (node (ref "LED4") (pin "1") (pinfunction "-_1") (pintype "unspecified"))
      (node (ref "Q2") (pin "4") (pinfunction "G2_4") (pintype "unspecified"))
    )
    (net (code "69") (name "Net-(LED5-+)") (class "Default")
      (node (ref "LED5") (pin "2") (pinfunction "+_2") (pintype "unspecified"))
      (node (ref "RN5") (pin "8") (pinfunction "8_8") (pintype "input"))
    )
    (net (code "70") (name "Net-(LED5--)") (class "Default")
      (node (ref "LED5") (pin "1") (pinfunction "-_1") (pintype "unspecified"))
      (node (ref "Q3") (pin "6") (pinfunction "G1_6") (pintype "unspecified"))
    )
    (net (code "71") (name "Net-(LED6-+)") (class "Default")
      (node (ref "LED6") (pin "2") (pinfunction "+_2") (pintype "unspecified"))
      (node (ref "RN5") (pin "7") (pinfunction "7_7") (pintype "input"))
    )
    (net (code "72") (name "Net-(LED6--)") (class "Default")
      (node (ref "LED6") (pin "1") (pinfunction "-_1") (pintype "unspecified"))
      (node (ref "Q3") (pin "4") (pinfunction "G2_4") (pintype "unspecified"))
    )
    (net (code "73") (name "Net-(LED7-+)") (class "Default")
      (node (ref "LED7") (pin "2") (pinfunction "+_2") (pintype "unspecified"))
      (node (ref "RN5") (pin "6") (pinfunction "6_6") (pintype "input"))
    )
    (net (code "74") (name "Net-(LED7--)") (class "Default")
      (node (ref "LED7") (pin "1") (pinfunction "-_1") (pintype "unspecified"))
      (node (ref "Q4") (pin "6") (pinfunction "G1_6") (pintype "unspecified"))
    )
    (net (code "75") (name "Net-(LED8-+)") (class "Default")
      (node (ref "LED8") (pin "2") (pinfunction "+_2") (pintype "unspecified"))
      (node (ref "RN5") (pin "5") (pinfunction "5_5") (pintype "input"))
    )
    (net (code "76") (name "Net-(LED8--)") (class "Default")
      (node (ref "LED8") (pin "1") (pinfunction "-_1") (pintype "unspecified"))
      (node (ref "Q4") (pin "4") (pinfunction "G2_4") (pintype "unspecified"))
    )
    (net (code "77") (name "Net-(LED9-+)") (class "Default")
      (node (ref "LED9") (pin "2") (pinfunction "+_2") (pintype "unspecified"))
      (node (ref "RN6") (pin "8") (pinfunction "8_8") (pintype "input"))
    )
    (net (code "78") (name "Net-(LED9--)") (class "Default")
      (node (ref "LED9") (pin "1") (pinfunction "-_1") (pintype "unspecified"))
      (node (ref "Q5") (pin "6") (pinfunction "G1_6") (pintype "unspecified"))
    )
    (net (code "79") (name "Net-(LED10-+)") (class "Default")
      (node (ref "LED10") (pin "2") (pinfunction "+_2") (pintype "unspecified"))
      (node (ref "RN6") (pin "7") (pinfunction "7_7") (pintype "input"))
    )
    (net (code "80") (name "Net-(LED10--)") (class "Default")
      (node (ref "LED10") (pin "1") (pinfunction "-_1") (pintype "unspecified"))
      (node (ref "Q5") (pin "4") (pinfunction "G2_4") (pintype "unspecified"))
    )
    (net (code "81") (name "Net-(LED11-+)") (class "Default")
      (node (ref "LED11") (pin "2") (pinfunction "+_2") (pintype "unspecified"))
      (node (ref "RN6") (pin "6") (pinfunction "6_6") (pintype "input"))
    )
    (net (code "82") (name "Net-(LED11--)") (class "Default")
      (node (ref "LED11") (pin "1") (pinfunction "-_1") (pintype "unspecified"))
      (node (ref "Q6") (pin "6") (pinfunction "G1_6") (pintype "unspecified"))
    )
    (net (code "83") (name "Net-(LED12-+)") (class "Default")
      (node (ref "LED12") (pin "2") (pinfunction "+_2") (pintype "unspecified"))
      (node (ref "RN6") (pin "5") (pinfunction "5_5") (pintype "input"))
    )
    (net (code "84") (name "Net-(LED12--)") (class "Default")
      (node (ref "LED12") (pin "1") (pinfunction "-_1") (pintype "unspecified"))
      (node (ref "Q6") (pin "4") (pinfunction "G2_4") (pintype "unspecified"))
    )
    (net (code "85") (name "Net-(LED13-+)") (class "Default")
      (node (ref "LED13") (pin "2") (pinfunction "+_2") (pintype "unspecified"))
      (node (ref "R8") (pin "1") (pinfunction "1_1") (pintype "input"))
    )
    (net (code "86") (name "Net-(LED13--)") (class "Default")
      (node (ref "LED13") (pin "1") (pinfunction "-_1") (pintype "unspecified"))
      (node (ref "R9") (pin "1") (pinfunction "1_1") (pintype "input"))
    )
    (net (code "87") (name "Net-(LED14-A)") (class "Default")
      (node (ref "LED14") (pin "1") (pinfunction "A_1") (pintype "input"))
      (node (ref "RN10") (pin "4") (pinfunction "4_4") (pintype "input"))
    )
    (net (code "88") (name "Net-(LED14-C)") (class "Default")
      (node (ref "LED14") (pin "2") (pinfunction "C_2") (pintype "input"))
      (node (ref "RN7") (pin "1") (pinfunction "1_1") (pintype "input"))
    )
    (net (code "89") (name "Net-(LED15-A)") (class "Default")
      (node (ref "LED15") (pin "1") (pinfunction "A_1") (pintype "input"))
      (node (ref "RN10") (pin "3") (pinfunction "3_3") (pintype "input"))
    )
    (net (code "90") (name "Net-(LED15-C)") (class "Default")
      (node (ref "LED15") (pin "2") (pinfunction "C_2") (pintype "input"))
      (node (ref "RN7") (pin "2") (pinfunction "2_2") (pintype "input"))
    )
    (net (code "91") (name "Net-(LED16-A)") (class "Default")
      (node (ref "LED16") (pin "1") (pinfunction "A_1") (pintype "input"))
      (node (ref "RN10") (pin "2") (pinfunction "2_2") (pintype "input"))
    )
    (net (code "92") (name "Net-(LED16-C)") (class "Default")
      (node (ref "LED16") (pin "2") (pinfunction "C_2") (pintype "input"))
      (node (ref "RN7") (pin "3") (pinfunction "3_3") (pintype "input"))
    )
    (net (code "93") (name "Net-(LED17-A)") (class "Default")
      (node (ref "LED17") (pin "1") (pinfunction "A_1") (pintype "input"))
      (node (ref "RN10") (pin "1") (pinfunction "1_1") (pintype "input"))
    )
    (net (code "94") (name "Net-(LED17-C)") (class "Default")
      (node (ref "LED17") (pin "2") (pinfunction "C_2") (pintype "input"))
      (node (ref "RN7") (pin "4") (pinfunction "4_4") (pintype "input"))
    )
    (net (code "95") (name "Net-(LED18-A)") (class "Default")
      (node (ref "LED18") (pin "1") (pinfunction "A_1") (pintype "input"))
      (node (ref "RN11") (pin "4") (pinfunction "4_4") (pintype "input"))
    )
    (net (code "96") (name "Net-(LED18-C)") (class "Default")
      (node (ref "LED18") (pin "2") (pinfunction "C_2") (pintype "input"))
      (node (ref "RN8") (pin "1") (pinfunction "1_1") (pintype "input"))
    )
    (net (code "97") (name "Net-(LED19-A)") (class "Default")
      (node (ref "LED19") (pin "1") (pinfunction "A_1") (pintype "input"))
      (node (ref "RN11") (pin "3") (pinfunction "3_3") (pintype "input"))
    )
    (net (code "98") (name "Net-(LED19-C)") (class "Default")
      (node (ref "LED19") (pin "2") (pinfunction "C_2") (pintype "input"))
      (node (ref "RN8") (pin "2") (pinfunction "2_2") (pintype "input"))
    )
    (net (code "99") (name "Net-(LED20-A)") (class "Default")
      (node (ref "LED20") (pin "1") (pinfunction "A_1") (pintype "input"))
      (node (ref "RN11") (pin "2") (pinfunction "2_2") (pintype "input"))
    )
    (net (code "100") (name "Net-(LED20-C)") (class "Default")
      (node (ref "LED20") (pin "2") (pinfunction "C_2") (pintype "input"))
      (node (ref "RN8") (pin "3") (pinfunction "3_3") (pintype "input"))
    )
    (net (code "101") (name "Net-(LED21-A)") (class "Default")
      (node (ref "LED21") (pin "1") (pinfunction "A_1") (pintype "input"))
      (node (ref "RN11") (pin "1") (pinfunction "1_1") (pintype "input"))
    )
    (net (code "102") (name "Net-(LED21-C)") (class "Default")
      (node (ref "LED21") (pin "2") (pinfunction "C_2") (pintype "input"))
      (node (ref "RN8") (pin "4") (pinfunction "4_4") (pintype "input"))
    )
    (net (code "103") (name "Net-(LED22-A)") (class "Default")
      (node (ref "LED22") (pin "1") (pinfunction "A_1") (pintype "input"))
      (node (ref "RN12") (pin "4") (pinfunction "4_4") (pintype "input"))
    )
    (net (code "104") (name "Net-(LED22-C)") (class "Default")
      (node (ref "LED22") (pin "2") (pinfunction "C_2") (pintype "input"))
      (node (ref "RN9") (pin "1") (pinfunction "1_1") (pintype "input"))
    )
    (net (code "105") (name "Net-(LED23-A)") (class "Default")
      (node (ref "LED23") (pin "1") (pinfunction "A_1") (pintype "input"))
      (node (ref "RN12") (pin "3") (pinfunction "3_3") (pintype "input"))
    )
    (net (code "106") (name "Net-(LED23-C)") (class "Default")
      (node (ref "LED23") (pin "2") (pinfunction "C_2") (pintype "input"))
      (node (ref "RN9") (pin "2") (pinfunction "2_2") (pintype "input"))
    )
    (net (code "107") (name "Net-(LED24-A)") (class "Default")
      (node (ref "LED24") (pin "1") (pinfunction "A_1") (pintype "input"))
      (node (ref "RN12") (pin "2") (pinfunction "2_2") (pintype "input"))
    )
    (net (code "108") (name "Net-(LED24-C)") (class "Default")
      (node (ref "LED24") (pin "2") (pinfunction "C_2") (pintype "input"))
      (node (ref "RN9") (pin "3") (pinfunction "3_3") (pintype "input"))
    )
    (net (code "109") (name "Net-(LED25-A)") (class "Default")
      (node (ref "LED25") (pin "1") (pinfunction "A_1") (pintype "input"))
      (node (ref "RN12") (pin "1") (pinfunction "1_1") (pintype "input"))
    )
    (net (code "110") (name "Net-(LED25-C)") (class "Default")
      (node (ref "LED25") (pin "2") (pinfunction "C_2") (pintype "input"))
      (node (ref "RN9") (pin "4") (pinfunction "4_4") (pintype "input"))
    )
    (net (code "111") (name "Net-(P1-Co-A)") (class "Default")
      (node (ref "P1") (pin "2") (pinfunction "Co-A_2") (pintype "unspecified"))
      (node (ref "U5") (pin "3") (pinfunction "Co-A_3") (pintype "unspecified"))
    )
    (net (code "112") (name "Net-(R1-Pad1)") (class "Default")
      (node (ref "R1") (pin "1") (pinfunction "1_1") (pintype "input"))
      (node (ref "R2") (pin "2") (pinfunction "2_2") (pintype "input"))
      (node (ref "R3") (pin "2") (pinfunction "2_2") (pintype "input"))
    )
    (net (code "113") (name "Net-(R3-Pad1)") (class "Default")
      (node (ref "R3") (pin "1") (pinfunction "1_1") (pintype "input"))
      (node (ref "R4") (pin "2") (pinfunction "2_2") (pintype "input"))
      (node (ref "R5") (pin "2") (pinfunction "2_2") (pintype "input"))
    )
    (net (code "114") (name "Net-(R7-Pad2)") (class "Default")
      (node (ref "R7") (pin "2") (pinfunction "2_2") (pintype "input"))
      (node (ref "U11") (pin "1") (pinfunction "1_1") (pintype "unspecified"))
    )
    (net (code "115") (name "Net-(R10-Pad2)") (class "Default")
      (node (ref "R10") (pin "2") (pinfunction "2_2") (pintype "input"))
      (node (ref "R8") (pin "2") (pinfunction "2_2") (pintype "input"))
      (node (ref "U11") (pin "3") (pinfunction "3_3") (pintype "unspecified"))
    )
    (net (code "116") (name "Net-(RN4-Pad1)") (class "Default")
      (node (ref "RN4") (pin "1") (pinfunction "1_1") (pintype "input"))
      (node (ref "U8") (pin "15") (pinfunction "15_15") (pintype "input"))
    )
    (net (code "117") (name "Net-(RN4-Pad2)") (class "Default")
      (node (ref "RN4") (pin "2") (pinfunction "2_2") (pintype "input"))
      (node (ref "U8") (pin "13") (pinfunction "13_13") (pintype "input"))
    )
    (net (code "118") (name "Net-(RN4-Pad3)") (class "Default")
      (node (ref "RN4") (pin "3") (pinfunction "3_3") (pintype "input"))
      (node (ref "U8") (pin "11") (pinfunction "11_11") (pintype "input"))
    )
    (net (code "119") (name "Net-(RN4-Pad4)") (class "Default")
      (node (ref "RN4") (pin "4") (pinfunction "4_4") (pintype "input"))
      (node (ref "U8") (pin "9") (pinfunction "9_9") (pintype "input"))
    )
    (net (code "120") (name "Net-(RN5-Pad1)") (class "Default")
      (node (ref "RN5") (pin "1") (pinfunction "1_1") (pintype "input"))
      (node (ref "U9") (pin "15") (pinfunction "15_15") (pintype "input"))
    )
    (net (code "121") (name "Net-(RN5-Pad2)") (class "Default")
      (node (ref "RN5") (pin "2") (pinfunction "2_2") (pintype "input"))
      (node (ref "U9") (pin "13") (pinfunction "13_13") (pintype "input"))
    )
    (net (code "122") (name "Net-(RN5-Pad3)") (class "Default")
      (node (ref "RN5") (pin "3") (pinfunction "3_3") (pintype "input"))
      (node (ref "U9") (pin "11") (pinfunction "11_11") (pintype "input"))
    )
    (net (code "123") (name "Net-(RN5-Pad4)") (class "Default")
      (node (ref "RN5") (pin "4") (pinfunction "4_4") (pintype "input"))
      (node (ref "U9") (pin "9") (pinfunction "9_9") (pintype "input"))
    )
    (net (code "124") (name "Net-(RN6-Pad1)") (class "Default")
      (node (ref "RN6") (pin "1") (pinfunction "1_1") (pintype "input"))
      (node (ref "U10") (pin "15") (pinfunction "15_15") (pintype "input"))
    )
    (net (code "125") (name "Net-(RN6-Pad2)") (class "Default")
      (node (ref "RN6") (pin "2") (pinfunction "2_2") (pintype "input"))
      (node (ref "U10") (pin "13") (pinfunction "13_13") (pintype "input"))
    )
    (net (code "126") (name "Net-(RN6-Pad3)") (class "Default")
      (node (ref "RN6") (pin "3") (pinfunction "3_3") (pintype "input"))
      (node (ref "U10") (pin "11") (pinfunction "11_11") (pintype "input"))
    )
    (net (code "127") (name "Net-(RN6-Pad4)") (class "Default")
      (node (ref "RN6") (pin "4") (pinfunction "4_4") (pintype "input"))
      (node (ref "U10") (pin "9") (pinfunction "9_9") (pintype "input"))
    )
    (net (code "128") (name "Net-(RN7-Pad5)") (class "Default")
      (node (ref "RN7") (pin "5") (pinfunction "5_5") (pintype "input"))
      (node (ref "U8") (pin "7") (pinfunction "7_7") (pintype "input"))
    )
    (net (code "129") (name "Net-(RN7-Pad6)") (class "Default")
      (node (ref "RN7") (pin "6") (pinfunction "6_6") (pintype "input"))
      (node (ref "U8") (pin "5") (pinfunction "5_5") (pintype "input"))
    )
    (net (code "130") (name "Net-(RN7-Pad7)") (class "Default")
      (node (ref "RN7") (pin "7") (pinfunction "7_7") (pintype "input"))
      (node (ref "U8") (pin "3") (pinfunction "3_3") (pintype "input"))
    )
    (net (code "131") (name "Net-(RN7-Pad8)") (class "Default")
      (node (ref "RN7") (pin "8") (pinfunction "8_8") (pintype "input"))
      (node (ref "U8") (pin "1") (pinfunction "1_1") (pintype "input"))
    )
    (net (code "132") (name "Net-(RN8-Pad5)") (class "Default")
      (node (ref "RN8") (pin "5") (pinfunction "5_5") (pintype "input"))
      (node (ref "U9") (pin "7") (pinfunction "7_7") (pintype "input"))
    )
    (net (code "133") (name "Net-(RN8-Pad6)") (class "Default")
      (node (ref "RN8") (pin "6") (pinfunction "6_6") (pintype "input"))
      (node (ref "U9") (pin "5") (pinfunction "5_5") (pintype "input"))
    )
    (net (code "134") (name "Net-(RN8-Pad7)") (class "Default")
      (node (ref "RN8") (pin "7") (pinfunction "7_7") (pintype "input"))
      (node (ref "U9") (pin "3") (pinfunction "3_3") (pintype "input"))
    )
    (net (code "135") (name "Net-(RN8-Pad8)") (class "Default")
      (node (ref "RN8") (pin "8") (pinfunction "8_8") (pintype "input"))
      (node (ref "U9") (pin "1") (pinfunction "1_1") (pintype "input"))
    )
    (net (code "136") (name "Net-(RN9-Pad5)") (class "Default")
      (node (ref "RN9") (pin "5") (pinfunction "5_5") (pintype "input"))
      (node (ref "U10") (pin "7") (pinfunction "7_7") (pintype "input"))
    )
    (net (code "137") (name "Net-(RN9-Pad6)") (class "Default")
      (node (ref "RN9") (pin "6") (pinfunction "6_6") (pintype "input"))
      (node (ref "U10") (pin "5") (pinfunction "5_5") (pintype "input"))
    )
    (net (code "138") (name "Net-(RN9-Pad7)") (class "Default")
      (node (ref "RN9") (pin "7") (pinfunction "7_7") (pintype "input"))
      (node (ref "U10") (pin "3") (pinfunction "3_3") (pintype "input"))
    )
    (net (code "139") (name "Net-(RN9-Pad8)") (class "Default")
      (node (ref "RN9") (pin "8") (pinfunction "8_8") (pintype "input"))
      (node (ref "U10") (pin "1") (pinfunction "1_1") (pintype "input"))
    )
    (net (code "140") (name "Net-(U1-HR-)") (class "Default")
      (node (ref "RN3") (pin "6") (pinfunction "6_6") (pintype "input"))
      (node (ref "U1") (pin "22") (pinfunction "HR-_22") (pintype "unspecified"))
    )
    (net (code "141") (name "Net-(U1-PR-)") (class "Default")
      (node (ref "RN3") (pin "7") (pinfunction "7_7") (pintype "input"))
      (node (ref "U1") (pin "20") (pinfunction "PR-_20") (pintype "unspecified"))
    )
    (net (code "142") (name "Net-(U1-V1-)") (class "Default")
      (node (ref "RN1") (pin "8") (pinfunction "8_8") (pintype "input"))
      (node (ref "U1") (pin "2") (pinfunction "V1-_2") (pintype "unspecified"))
    )
    (net (code "143") (name "Net-(U1-V2-)") (class "Default")
      (node (ref "RN1") (pin "7") (pinfunction "7_7") (pintype "input"))
      (node (ref "U1") (pin "4") (pinfunction "V2-_4") (pintype "unspecified"))
    )
    (net (code "144") (name "Net-(U1-V3-)") (class "Default")
      (node (ref "RN1") (pin "6") (pinfunction "6_6") (pintype "input"))
      (node (ref "U1") (pin "6") (pinfunction "V3-_6") (pintype "unspecified"))
    )
    (net (code "145") (name "Net-(U1-V4-)") (class "Default")
      (node (ref "RN1") (pin "5") (pinfunction "5_5") (pintype "input"))
      (node (ref "U1") (pin "8") (pinfunction "V4-_8") (pintype "unspecified"))
    )
    (net (code "146") (name "Net-(U1-V5-)") (class "Default")
      (node (ref "RN2") (pin "8") (pinfunction "8_8") (pintype "input"))
      (node (ref "U1") (pin "10") (pinfunction "V5-_10") (pintype "unspecified"))
    )
    (net (code "147") (name "Net-(U1-V6-)") (class "Default")
      (node (ref "RN2") (pin "7") (pinfunction "7_7") (pintype "input"))
      (node (ref "U1") (pin "12") (pinfunction "V6-_12") (pintype "unspecified"))
    )
    (net (code "148") (name "Net-(U1-V7-)") (class "Default")
      (node (ref "RN2") (pin "6") (pinfunction "6_6") (pintype "input"))
      (node (ref "U1") (pin "14") (pinfunction "V7-_14") (pintype "unspecified"))
    )
    (net (code "149") (name "Net-(U1-V8-)") (class "Default")
      (node (ref "RN2") (pin "5") (pinfunction "5_5") (pintype "input"))
      (node (ref "U1") (pin "16") (pinfunction "V8-_16") (pintype "unspecified"))
    )
    (net (code "150") (name "Net-(U1-V9-)") (class "Default")
      (node (ref "RN3") (pin "8") (pinfunction "8_8") (pintype "input"))
      (node (ref "U1") (pin "18") (pinfunction "V9-_18") (pintype "unspecified"))
    )
    (net (code "151") (name "Net-(U2-O-)") (class "Default")
      (node (ref "RN3") (pin "5") (pinfunction "5_5") (pintype "input"))
      (node (ref "U2") (pin "2") (pinfunction "O-_2") (pintype "unspecified"))
    )
    (net (code "152") (name "Net-(U3-SW1+)") (class "Default")
      (node (ref "RN16") (pin "1") (pinfunction "1_1") (pintype "input"))
      (node (ref "RN17") (pin "8") (pinfunction "8_8") (pintype "input"))
      (node (ref "U3") (pin "1") (pinfunction "SW1+_1") (pintype "unspecified"))
    )
    (net (code "153") (name "Net-(U3-SW2+)") (class "Default")
      (node (ref "RN16") (pin "2") (pinfunction "2_2") (pintype "input"))
      (node (ref "RN17") (pin "7") (pinfunction "7_7") (pintype "input"))
      (node (ref "U3") (pin "3") (pinfunction "SW2+_3") (pintype "unspecified"))
    )
    (net (code "154") (name "Net-(U3-SW3+)") (class "Default")
      (node (ref "RN16") (pin "3") (pinfunction "3_3") (pintype "input"))
      (node (ref "RN17") (pin "6") (pinfunction "6_6") (pintype "input"))
      (node (ref "U3") (pin "5") (pinfunction "SW3+_5") (pintype "unspecified"))
    )
    (net (code "155") (name "Net-(U3-SW4+)") (class "Default")
      (node (ref "RN16") (pin "4") (pinfunction "4_4") (pintype "input"))
      (node (ref "RN17") (pin "5") (pinfunction "5_5") (pintype "input"))
      (node (ref "U3") (pin "7") (pinfunction "SW4+_7") (pintype "unspecified"))
    )
    (net (code "156") (name "Net-(U4-D0)") (class "Default")
      (node (ref "U4") (pin "1") (pinfunction "D0_1") (pintype "unspecified"))
      (node (ref "U5") (pin "7") (pinfunction "D0_7") (pintype "unspecified"))
    )
    (net (code "157") (name "Net-(U4-D1)") (class "Default")
      (node (ref "U4") (pin "2") (pinfunction "D1_2") (pintype "unspecified"))
      (node (ref "U5") (pin "8") (pinfunction "D1_8") (pintype "unspecified"))
    )
    (net (code "158") (name "Net-(U4-D2)") (class "Default")
      (node (ref "U4") (pin "3") (pinfunction "D2_3") (pintype "unspecified"))
      (node (ref "U5") (pin "9") (pinfunction "D2_9") (pintype "unspecified"))
    )
    (net (code "159") (name "Net-(U4-D3)") (class "Default")
      (node (ref "U4") (pin "4") (pinfunction "D3_4") (pintype "unspecified"))
      (node (ref "U5") (pin "10") (pinfunction "D3_10") (pintype "unspecified"))
    )
    (net (code "160") (name "Net-(U12-Vout)") (class "Default")
      (node (ref "R7") (pin "1") (pinfunction "1_1") (pintype "input"))
      (node (ref "U12") (pin "3") (pinfunction "Vout_3") (pintype "unspecified"))
    )
    (net (code "161") (name "RPI-GND") (class "Default")
      (node (ref "C1") (pin "2") (pinfunction "2_2") (pintype "input"))
      (node (ref "C2") (pin "2") (pinfunction "2_2") (pintype "input"))
      (node (ref "C3") (pin "2") (pinfunction "2_2") (pintype "input"))
      (node (ref "C4") (pin "2") (pinfunction "2_2") (pintype "input"))
      (node (ref "JP1") (pin "14") (pinfunction "GND_14") (pintype "unspecified"))
      (node (ref "JP1") (pin "20") (pinfunction "GND_20") (pintype "unspecified"))
      (node (ref "JP1") (pin "25") (pinfunction "GND_25") (pintype "unspecified"))
      (node (ref "JP1") (pin "30") (pinfunction "GND_30") (pintype "unspecified"))
      (node (ref "JP1") (pin "34") (pinfunction "GND_34") (pintype "unspecified"))
      (node (ref "JP1") (pin "39") (pinfunction "GND_39") (pintype "unspecified"))
      (node (ref "JP1") (pin "6") (pinfunction "GND_6") (pintype "unspecified"))
      (node (ref "JP1") (pin "9") (pinfunction "GND_9") (pintype "unspecified"))
      (node (ref "P1") (pin "3") (pinfunction "GND_3") (pintype "unspecified"))
      (node (ref "R10") (pin "1") (pinfunction "1_1") (pintype "input"))
      (node (ref "RN13") (pin "5") (pinfunction "5_5") (pintype "input"))
      (node (ref "RN13") (pin "6") (pinfunction "6_6") (pintype "input"))
      (node (ref "RN13") (pin "7") (pinfunction "7_7") (pintype "input"))
      (node (ref "RN13") (pin "8") (pinfunction "8_8") (pintype "input"))
      (node (ref "RN14") (pin "5") (pinfunction "5_5") (pintype "input"))
      (node (ref "RN14") (pin "6") (pinfunction "6_6") (pintype "input"))
      (node (ref "RN14") (pin "7") (pinfunction "7_7") (pintype "input"))
      (node (ref "RN14") (pin "8") (pinfunction "8_8") (pintype "input"))
      (node (ref "RN15") (pin "5") (pinfunction "5_5") (pintype "input"))
      (node (ref "RN15") (pin "6") (pinfunction "6_6") (pintype "input"))
      (node (ref "RN15") (pin "7") (pinfunction "7_7") (pintype "input"))
      (node (ref "RN15") (pin "8") (pinfunction "8_8") (pintype "input"))
      (node (ref "U10") (pin "2") (pinfunction "2_2") (pintype "input"))
      (node (ref "U10") (pin "4") (pinfunction "4_4") (pintype "input"))
      (node (ref "U10") (pin "6") (pinfunction "6_6") (pintype "input"))
      (node (ref "U10") (pin "8") (pinfunction "8_8") (pintype "input"))
      (node (ref "U13") (pin "10") (pinfunction "GND_10") (pintype "unspecified"))
      (node (ref "U3") (pin "2") (pinfunction "SW1-_2") (pintype "unspecified"))
      (node (ref "U3") (pin "4") (pinfunction "SW2-_4") (pintype "unspecified"))
      (node (ref "U3") (pin "6") (pinfunction "SW3-_6") (pintype "unspecified"))
      (node (ref "U3") (pin "8") (pinfunction "SW4-_8") (pintype "unspecified"))
      (node (ref "U5") (pin "1") (pinfunction "GND_1") (pintype "unspecified"))
      (node (ref "U5") (pin "16") (pinfunction "Bp-_16") (pintype "unspecified"))
      (node (ref "U5") (pin "5") (pinfunction "RW-S_5") (pintype "unspecified"))
      (node (ref "U8") (pin "2") (pinfunction "2_2") (pintype "input"))
      (node (ref "U8") (pin "4") (pinfunction "4_4") (pintype "input"))
      (node (ref "U8") (pin "6") (pinfunction "6_6") (pintype "input"))
      (node (ref "U8") (pin "8") (pinfunction "8_8") (pintype "input"))
      (node (ref "U9") (pin "2") (pinfunction "2_2") (pintype "input"))
      (node (ref "U9") (pin "4") (pinfunction "4_4") (pintype "input"))
      (node (ref "U9") (pin "6") (pinfunction "6_6") (pintype "input"))
      (node (ref "U9") (pin "8") (pinfunction "8_8") (pintype "input"))
    )
  )
)
